# Microcontroller_With_Power_Supply_Module.net
KiCad netlist of a schematic drawn in EAGLE
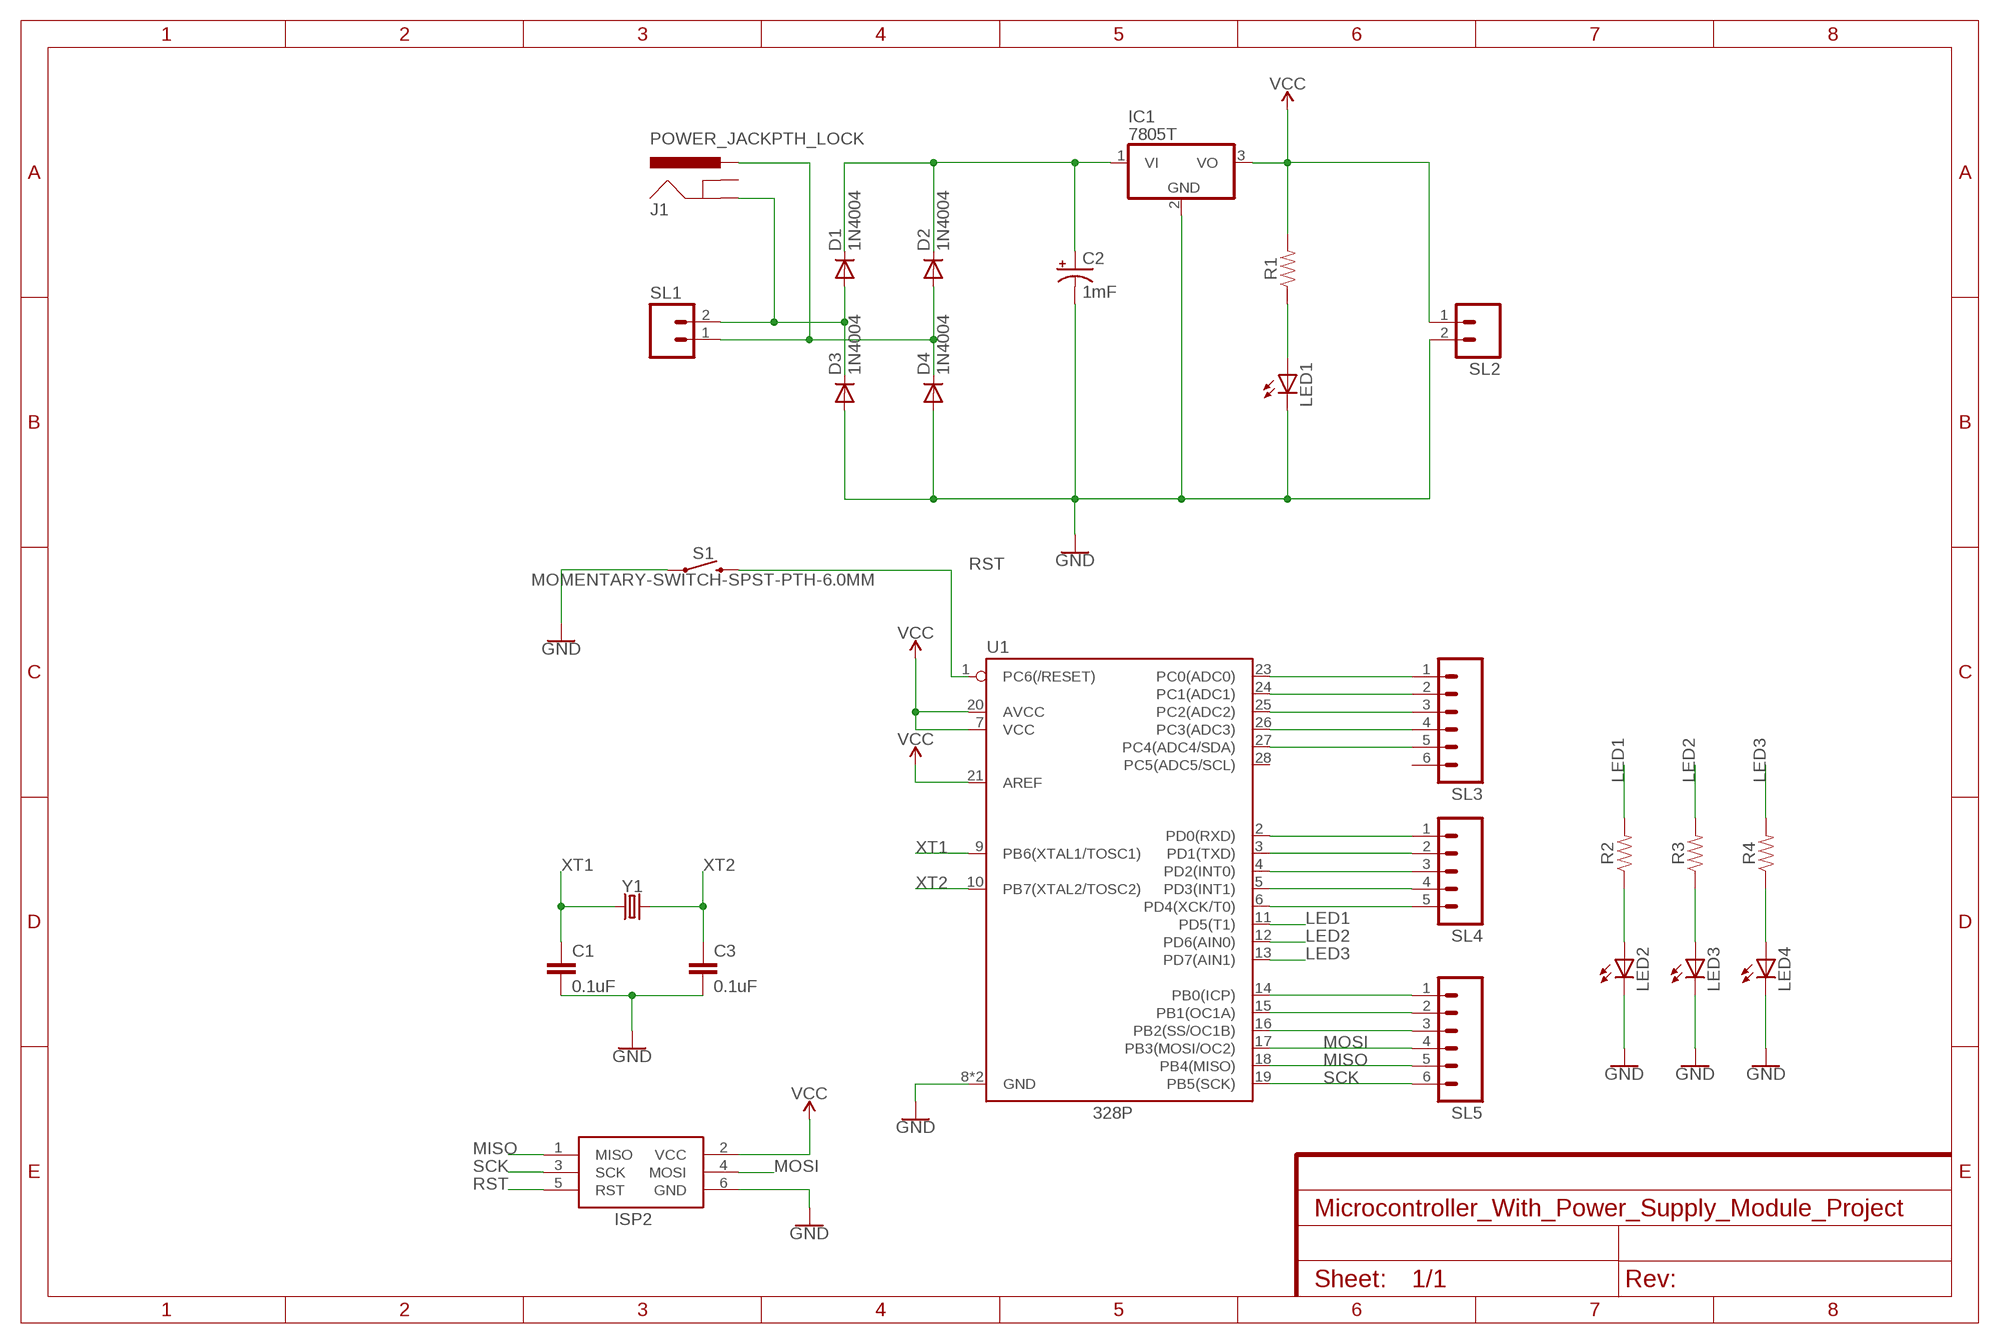
[diagram p0: schematic, sheet 1]

(export (version "E")
  (design (tool "Eeschema 10.0.6"))
  (components
    (comp (ref "C1")
      (value "0.1uF")
      (footprint "eagle-import:CAP-PTH-SMALL-KIT")
      (libsource (lib "eagle-import") (part "0.1UF-KIT-EZ-50V-20%"))
    )
    (comp (ref "C2")
      (value "1mF")
      (footprint "eagle-import:CPOL-RADIAL-5MM-10MM")
      (libsource (lib "eagle-import") (part "1000UF-RADIAL-5MM-25V-20%"))
    )
    (comp (ref "C3")
      (value "0.1uF")
      (footprint "eagle-import:CAP-PTH-SMALL-KIT")
      (libsource (lib "eagle-import") (part "0.1UF-KIT-EZ-50V-20%"))
    )
    (comp (ref "D1")
      (value "1N4004")
      (footprint "eagle-import:DO41-10")
      (libsource (lib "eagle-import") (part "1N4004"))
    )
    (comp (ref "D2")
      (value "1N4004")
      (footprint "eagle-import:DO41-10")
      (libsource (lib "eagle-import") (part "1N4004"))
    )
    (comp (ref "D3")
      (value "1N4004")
      (footprint "eagle-import:DO41-10")
      (libsource (lib "eagle-import") (part "1N4004"))
    )
    (comp (ref "D4")
      (value "1N4004")
      (footprint "eagle-import:DO41-10")
      (libsource (lib "eagle-import") (part "1N4004"))
    )
    (comp (ref "IC1")
      (value "7805T")
      (footprint "eagle-import:TO220H")
      (libsource (lib "eagle-import") (part "78T05"))
    )
    (comp (ref "ISP2")
      (value "AVRISP-6")
      (footprint "eagle-import:AVRISP")
      (libsource (lib "eagle-import") (part "AVRISP-6"))
    )
    (comp (ref "J1")
      (value "POWER_JACKPTH_LOCK")
      (footprint "eagle-import:POWER_JACK_PTH_LOCK")
      (libsource (lib "eagle-import") (part "POWER_JACKPTH_LOCK"))
    )
    (comp (ref "LED1")
      (value "LED5MM")
      (footprint "eagle-import:LED5MM")
      (libsource (lib "eagle-import") (part "LED5MM"))
    )
    (comp (ref "LED2")
      (value "LED3MM")
      (footprint "eagle-import:LED3MM")
      (libsource (lib "eagle-import") (part "LED3MM"))
    )
    (comp (ref "LED3")
      (value "LED3MM")
      (footprint "eagle-import:LED3MM")
      (libsource (lib "eagle-import") (part "LED3MM"))
    )
    (comp (ref "LED4")
      (value "LED3MM")
      (footprint "eagle-import:LED3MM")
      (libsource (lib "eagle-import") (part "LED3MM"))
    )
    (comp (ref "R1")
      (value "RESISTORAXIAL-0.3")
      (footprint "eagle-import:AXIAL-0.3")
      (libsource (lib "eagle-import") (part "RESISTORAXIAL-0.3"))
    )
    (comp (ref "R2")
      (value "RESISTORAXIAL-0.3")
      (footprint "eagle-import:AXIAL-0.3")
      (libsource (lib "eagle-import") (part "RESISTORAXIAL-0.3"))
    )
    (comp (ref "R3")
      (value "RESISTORAXIAL-0.3")
      (footprint "eagle-import:AXIAL-0.3")
      (libsource (lib "eagle-import") (part "RESISTORAXIAL-0.3"))
    )
    (comp (ref "R4")
      (value "RESISTORAXIAL-0.3")
      (footprint "eagle-import:AXIAL-0.3")
      (libsource (lib "eagle-import") (part "RESISTORAXIAL-0.3"))
    )
    (comp (ref "S1")
      (value "MOMENTARY-SWITCH-SPST-PTH-6.0MM")
      (footprint "eagle-import:TACTILE_SWITCH_PTH_6.0MM")
      (libsource (lib "eagle-import") (part "MOMENTARY-SWITCH-SPST-PTH-6.0MM"))
    )
    (comp (ref "SL1")
      (value "M02")
      (footprint "eagle-import:02P")
      (libsource (lib "eagle-import") (part "M02"))
    )
    (comp (ref "SL2")
      (value "M02")
      (footprint "eagle-import:02P")
      (libsource (lib "eagle-import") (part "M02"))
    )
    (comp (ref "SL3")
      (value "M06")
      (footprint "eagle-import:06P")
      (libsource (lib "eagle-import") (part "M06"))
    )
    (comp (ref "SL4")
      (value "M05")
      (footprint "eagle-import:05P")
      (libsource (lib "eagle-import") (part "M05"))
    )
    (comp (ref "SL5")
      (value "M06")
      (footprint "eagle-import:06P")
      (libsource (lib "eagle-import") (part "M06"))
    )
    (comp (ref "U1")
      (value "328P")
      (footprint "eagle-import:DIP28")
      (libsource (lib "eagle-import") (part "ATMEGA328P_PDIP"))
    )
    (comp (ref "Y1")
      (value "CRYSTALPTH-HC49US")
      (footprint "eagle-import:HC49US")
      (libsource (lib "eagle-import") (part "CRYSTALPTH-HC49US"))
    )
  )
  (nets
    (net (code "1") (name "/LED1") (class "Default")
      (node (ref "R2") (pin "P$2") (pinfunction "2_P$2") (pintype "passive"))
      (node (ref "U1") (pin "11") (pinfunction "PD5(T1)_11") (pintype "bidirectional"))
    )
    (net (code "2") (name "/LED2") (class "Default")
      (node (ref "R3") (pin "P$2") (pinfunction "2_P$2") (pintype "passive"))
      (node (ref "U1") (pin "12") (pinfunction "PD6(AIN0)_12") (pintype "bidirectional"))
    )
    (net (code "3") (name "/LED3") (class "Default")
      (node (ref "R4") (pin "P$2") (pinfunction "2_P$2") (pintype "passive"))
      (node (ref "U1") (pin "13") (pinfunction "PD7(AIN1)_13") (pintype "bidirectional"))
    )
    (net (code "4") (name "/MISO") (class "Default")
      (node (ref "ISP2") (pin "1") (pinfunction "MISO_1") (pintype "input"))
      (node (ref "SL5") (pin "5") (pinfunction "5_5") (pintype "passive"))
      (node (ref "U1") (pin "18") (pinfunction "PB4(MISO)_18") (pintype "bidirectional"))
    )
    (net (code "5") (name "/MOSI") (class "Default")
      (node (ref "ISP2") (pin "4") (pinfunction "MOSI_4") (pintype "output"))
      (node (ref "SL5") (pin "4") (pinfunction "4_4") (pintype "passive"))
      (node (ref "U1") (pin "17") (pinfunction "PB3(MOSI/OC2)_17") (pintype "bidirectional"))
    )
    (net (code "6") (name "/RST") (class "Default")
      (node (ref "ISP2") (pin "5") (pinfunction "RST_5") (pintype "output"))
      (node (ref "S1") (pin "3") (pinfunction "2_3") (pintype "passive"))
      (node (ref "U1") (pin "1") (pinfunction "PC6(/RESET)_1") (pintype "bidirectional"))
    )
    (net (code "7") (name "/SCK") (class "Default")
      (node (ref "ISP2") (pin "3") (pinfunction "SCK_3") (pintype "output"))
      (node (ref "SL5") (pin "6") (pinfunction "6_6") (pintype "passive"))
      (node (ref "U1") (pin "19") (pinfunction "PB5(SCK)_19") (pintype "bidirectional"))
    )
    (net (code "8") (name "/XT1") (class "Default")
      (node (ref "C1") (pin "1") (pinfunction "1_1") (pintype "passive"))
      (node (ref "U1") (pin "9") (pinfunction "PB6(XTAL1/TOSC1)_9") (pintype "bidirectional"))
      (node (ref "Y1") (pin "1") (pinfunction "1_1") (pintype "passive"))
    )
    (net (code "9") (name "/XT2") (class "Default")
      (node (ref "C3") (pin "1") (pinfunction "1_1") (pintype "passive"))
      (node (ref "U1") (pin "10") (pinfunction "PB7(XTAL2/TOSC2)_10") (pintype "bidirectional"))
      (node (ref "Y1") (pin "2") (pinfunction "2_2") (pintype "passive"))
    )
    (net (code "10") (name "GND") (class "Default")
      (node (ref "C1") (pin "2") (pinfunction "2_2") (pintype "passive"))
      (node (ref "C2") (pin "-") (pinfunction "-_-") (pintype "passive"))
      (node (ref "C3") (pin "2") (pinfunction "2_2") (pintype "passive"))
      (node (ref "D3") (pin "A") (pinfunction "A_A") (pintype "passive"))
      (node (ref "D4") (pin "A") (pinfunction "A_A") (pintype "passive"))
      (node (ref "IC1") (pin "2") (pinfunction "GND_2") (pintype "passive"))
      (node (ref "ISP2") (pin "6") (pinfunction "GND_6") (pintype "power_in"))
      (node (ref "LED1") (pin "K") (pinfunction "C_K") (pintype "passive"))
      (node (ref "LED2") (pin "K") (pinfunction "C_K") (pintype "passive"))
      (node (ref "LED3") (pin "K") (pinfunction "C_K") (pintype "passive"))
      (node (ref "LED4") (pin "K") (pinfunction "C_K") (pintype "passive"))
      (node (ref "S1") (pin "1") (pinfunction "1_1") (pintype "passive"))
      (node (ref "SL2") (pin "2") (pinfunction "2_2") (pintype "passive"))
      (node (ref "U1") (pin "22") (pinfunction "GND_22") (pintype "bidirectional"))
      (node (ref "U1") (pin "8") (pinfunction "GND_8") (pintype "bidirectional"))
    )
    (net (code "11") (name "Net-(D1-PadA)") (class "Default")
      (node (ref "D1") (pin "A") (pinfunction "A_A") (pintype "passive"))
      (node (ref "D3") (pin "C") (pinfunction "C_C") (pintype "passive"))
      (node (ref "J1") (pin "GND") (pinfunction "GND_GND") (pintype "bidirectional"))
      (node (ref "SL1") (pin "2") (pinfunction "2_2") (pintype "passive"))
    )
    (net (code "12") (name "Net-(D2-PadA)") (class "Default")
      (node (ref "D2") (pin "A") (pinfunction "A_A") (pintype "passive"))
      (node (ref "D4") (pin "C") (pinfunction "C_C") (pintype "passive"))
      (node (ref "J1") (pin "PWR") (pinfunction "PWR_PWR") (pintype "bidirectional"))
      (node (ref "SL1") (pin "1") (pinfunction "1_1") (pintype "passive"))
    )
    (net (code "13") (name "Net-(IC1-VI)") (class "Default")
      (node (ref "C2") (pin "+") (pinfunction "+_+") (pintype "passive"))
      (node (ref "D1") (pin "C") (pinfunction "C_C") (pintype "passive"))
      (node (ref "D2") (pin "C") (pinfunction "C_C") (pintype "passive"))
      (node (ref "IC1") (pin "1") (pinfunction "VI_1") (pintype "input"))
    )
    (net (code "14") (name "Net-(R1-1)") (class "Default")
      (node (ref "LED1") (pin "A") (pinfunction "A_A") (pintype "passive"))
      (node (ref "R1") (pin "P$1") (pinfunction "1_P$1") (pintype "passive"))
    )
    (net (code "15") (name "Net-(R2-1)") (class "Default")
      (node (ref "LED2") (pin "A") (pinfunction "A_A") (pintype "passive"))
      (node (ref "R2") (pin "P$1") (pinfunction "1_P$1") (pintype "passive"))
    )
    (net (code "16") (name "Net-(R3-1)") (class "Default")
      (node (ref "LED3") (pin "A") (pinfunction "A_A") (pintype "passive"))
      (node (ref "R3") (pin "P$1") (pinfunction "1_P$1") (pintype "passive"))
    )
    (net (code "17") (name "Net-(R4-1)") (class "Default")
      (node (ref "LED4") (pin "A") (pinfunction "A_A") (pintype "passive"))
      (node (ref "R4") (pin "P$1") (pinfunction "1_P$1") (pintype "passive"))
    )
    (net (code "18") (name "Net-(U1-PB0(ICP))") (class "Default")
      (node (ref "SL5") (pin "1") (pinfunction "1_1") (pintype "passive"))
      (node (ref "U1") (pin "14") (pinfunction "PB0(ICP)_14") (pintype "bidirectional"))
    )
    (net (code "19") (name "Net-(U1-PB1(OC1A))") (class "Default")
      (node (ref "SL5") (pin "2") (pinfunction "2_2") (pintype "passive"))
      (node (ref "U1") (pin "15") (pinfunction "PB1(OC1A)_15") (pintype "bidirectional"))
    )
    (net (code "20") (name "Net-(U1-PB2(SS{slash}OC1B))") (class "Default")
      (node (ref "SL5") (pin "3") (pinfunction "3_3") (pintype "passive"))
      (node (ref "U1") (pin "16") (pinfunction "PB2(SS/OC1B)_16") (pintype "bidirectional"))
    )
    (net (code "21") (name "Net-(U1-PC0(ADC0))") (class "Default")
      (node (ref "SL3") (pin "1") (pinfunction "1_1") (pintype "passive"))
      (node (ref "U1") (pin "23") (pinfunction "PC0(ADC0)_23") (pintype "bidirectional"))
    )
    (net (code "22") (name "Net-(U1-PC1(ADC1))") (class "Default")
      (node (ref "SL3") (pin "2") (pinfunction "2_2") (pintype "passive"))
      (node (ref "U1") (pin "24") (pinfunction "PC1(ADC1)_24") (pintype "bidirectional"))
    )
    (net (code "23") (name "Net-(U1-PC2(ADC2))") (class "Default")
      (node (ref "SL3") (pin "3") (pinfunction "3_3") (pintype "passive"))
      (node (ref "U1") (pin "25") (pinfunction "PC2(ADC2)_25") (pintype "bidirectional"))
    )
    (net (code "24") (name "Net-(U1-PC3(ADC3))") (class "Default")
      (node (ref "SL3") (pin "4") (pinfunction "4_4") (pintype "passive"))
      (node (ref "U1") (pin "26") (pinfunction "PC3(ADC3)_26") (pintype "bidirectional"))
    )
    (net (code "25") (name "Net-(U1-PC4(ADC4{slash}SDA))") (class "Default")
      (node (ref "SL3") (pin "5") (pinfunction "5_5") (pintype "passive"))
      (node (ref "U1") (pin "27") (pinfunction "PC4(ADC4/SDA)_27") (pintype "bidirectional"))
    )
    (net (code "26") (name "Net-(U1-PD0(RXD))") (class "Default")
      (node (ref "SL4") (pin "1") (pinfunction "1_1") (pintype "passive"))
      (node (ref "U1") (pin "2") (pinfunction "PD0(RXD)_2") (pintype "bidirectional"))
    )
    (net (code "27") (name "Net-(U1-PD1(TXD))") (class "Default")
      (node (ref "SL4") (pin "2") (pinfunction "2_2") (pintype "passive"))
      (node (ref "U1") (pin "3") (pinfunction "PD1(TXD)_3") (pintype "bidirectional"))
    )
    (net (code "28") (name "Net-(U1-PD2(INT0))") (class "Default")
      (node (ref "SL4") (pin "3") (pinfunction "3_3") (pintype "passive"))
      (node (ref "U1") (pin "4") (pinfunction "PD2(INT0)_4") (pintype "bidirectional"))
    )
    (net (code "29") (name "Net-(U1-PD3(INT1))") (class "Default")
      (node (ref "SL4") (pin "4") (pinfunction "4_4") (pintype "passive"))
      (node (ref "U1") (pin "5") (pinfunction "PD3(INT1)_5") (pintype "bidirectional"))
    )
    (net (code "30") (name "Net-(U1-PD4(XCK{slash}T0))") (class "Default")
      (node (ref "SL4") (pin "5") (pinfunction "5_5") (pintype "passive"))
      (node (ref "U1") (pin "6") (pinfunction "PD4(XCK/T0)_6") (pintype "bidirectional"))
    )
    (net (code "31") (name "VCC") (class "Default")
      (node (ref "IC1") (pin "3") (pinfunction "VO_3") (pintype "passive"))
      (node (ref "ISP2") (pin "2") (pinfunction "VCC_2") (pintype "power_in"))
      (node (ref "R1") (pin "P$2") (pinfunction "2_P$2") (pintype "passive"))
      (node (ref "SL2") (pin "1") (pinfunction "1_1") (pintype "passive"))
      (node (ref "U1") (pin "20") (pinfunction "AVCC_20") (pintype "bidirectional"))
      (node (ref "U1") (pin "21") (pinfunction "AREF_21") (pintype "bidirectional"))
      (node (ref "U1") (pin "7") (pinfunction "VCC_7") (pintype "bidirectional"))
    )
    (net (code "32") (name "unconnected-(J1-PadGNDBREAK)") (class "Default")
      (node (ref "J1") (pin "GNDBREAK") (pinfunction "GNDBREAK_GNDBREAK") (pintype "bidirectional"))
    )
    (net (code "33") (name "unconnected-(SL3-Pad6)") (class "Default")
      (node (ref "SL3") (pin "6") (pinfunction "6_6") (pintype "passive"))
    )
    (net (code "34") (name "unconnected-(U1-PC5(ADC5{slash}SCL)-Pad28)") (class "Default")
      (node (ref "U1") (pin "28") (pinfunction "PC5(ADC5/SCL)_28") (pintype "bidirectional"))
    )
  )
)
